# Tayloe_Detector_v3.net
KiCad netlist of a schematic drawn in EAGLE
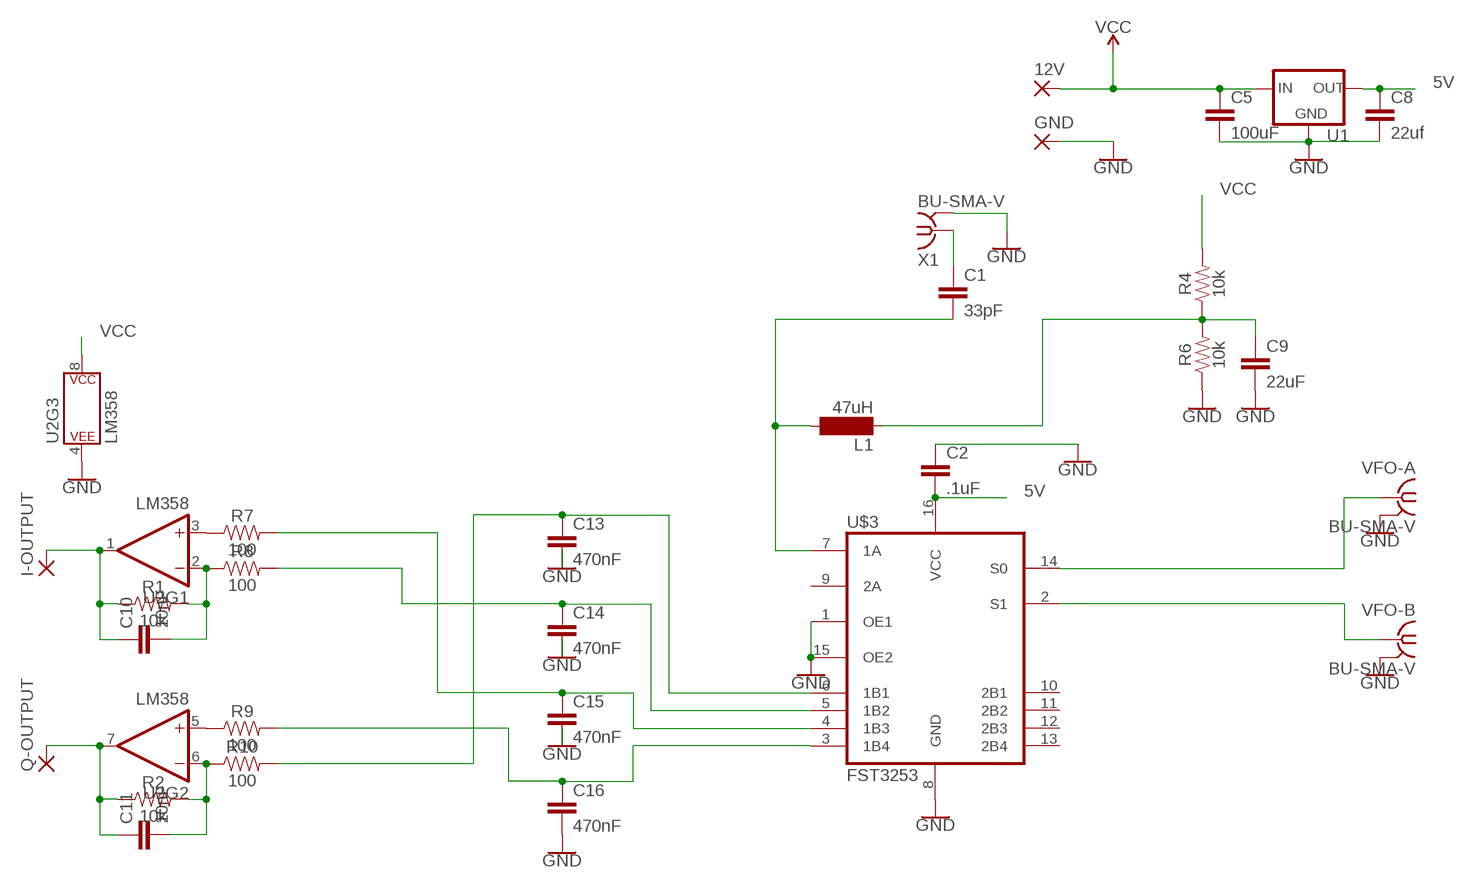
[diagram p0: schematic, sheet 1]

(export (version "E")
  (design (tool "Eeschema 10.0.6"))
  (components
    (comp (ref "12V")
      (value "3,17/1,1")
      (footprint "eagle-import:3,17_1,1")
      (libsource (lib "eagle-import") (part "3,17/1,1"))
    )
    (comp (ref "C1")
      (value "33pF")
      (footprint "eagle-import:C5B3.5")
      (libsource (lib "eagle-import") (part "C5/3.5"))
    )
    (comp (ref "C2")
      (value ".1uF")
      (footprint "eagle-import:C5B3.5")
      (libsource (lib "eagle-import") (part "C5/3.5"))
    )
    (comp (ref "C5")
      (value "100uF")
      (footprint "eagle-import:C5B3.5")
      (libsource (lib "eagle-import") (part "C5/3.5"))
    )
    (comp (ref "C8")
      (value "22uf")
      (footprint "eagle-import:C5B3.5")
      (libsource (lib "eagle-import") (part "C5/3.5"))
    )
    (comp (ref "C9")
      (value "22uF")
      (footprint "eagle-import:C5B3.5")
      (libsource (lib "eagle-import") (part "C5/3.5"))
    )
    (comp (ref "C10")
      (value "10nF")
      (footprint "eagle-import:C5B3.5")
      (libsource (lib "eagle-import") (part "C5/3.5"))
    )
    (comp (ref "C11")
      (value "10nF")
      (footprint "eagle-import:C5B3.5")
      (libsource (lib "eagle-import") (part "C5/3.5"))
    )
    (comp (ref "C13")
      (value "470nF")
      (footprint "eagle-import:C5B3.5")
      (libsource (lib "eagle-import") (part "C5/3.5"))
    )
    (comp (ref "C14")
      (value "470nF")
      (footprint "eagle-import:C5B3.5")
      (libsource (lib "eagle-import") (part "C5/3.5"))
    )
    (comp (ref "C15")
      (value "470nF")
      (footprint "eagle-import:C5B3.5")
      (libsource (lib "eagle-import") (part "C5/3.5"))
    )
    (comp (ref "C16")
      (value "470nF")
      (footprint "eagle-import:C5B3.5")
      (libsource (lib "eagle-import") (part "C5/3.5"))
    )
    (comp (ref "GND")
      (value "3,17/1,1")
      (footprint "eagle-import:3,17_1,1")
      (libsource (lib "eagle-import") (part "3,17/1,1"))
    )
    (comp (ref "I-OUTPUT")
      (value "3,17/1,1")
      (footprint "eagle-import:3,17_1,1")
      (libsource (lib "eagle-import") (part "3,17/1,1"))
    )
    (comp (ref "L1")
      (value "47uH")
      (footprint "eagle-import:BS75")
      (libsource (lib "eagle-import") (part "BS75"))
    )
    (comp (ref "Q-OUTPUT")
      (value "3,17/1,1")
      (footprint "eagle-import:3,17_1,1")
      (libsource (lib "eagle-import") (part "3,17/1,1"))
    )
    (comp (ref "R1")
      (value "10k")
      (footprint "eagle-import:AXIAL-0.3")
      (libsource (lib "eagle-import") (part "1KOHM-HORIZ-1/4W-1%"))
    )
    (comp (ref "R2")
      (value "10k")
      (footprint "eagle-import:AXIAL-0.3")
      (libsource (lib "eagle-import") (part "1KOHM-HORIZ-1/4W-1%"))
    )
    (comp (ref "R4")
      (value "10k")
      (footprint "eagle-import:AXIAL-0.3")
      (libsource (lib "eagle-import") (part "1KOHM-HORIZ-1/4W-1%"))
    )
    (comp (ref "R6")
      (value "10k")
      (footprint "eagle-import:AXIAL-0.3")
      (libsource (lib "eagle-import") (part "1KOHM-HORIZ-1/4W-1%"))
    )
    (comp (ref "R7")
      (value "100")
      (footprint "eagle-import:AXIAL-0.3")
      (libsource (lib "eagle-import") (part "1KOHM-HORIZ-1/4W-1%"))
    )
    (comp (ref "R8")
      (value "100")
      (footprint "eagle-import:AXIAL-0.3")
      (libsource (lib "eagle-import") (part "1KOHM-HORIZ-1/4W-1%"))
    )
    (comp (ref "R9")
      (value "100")
      (footprint "eagle-import:AXIAL-0.3")
      (libsource (lib "eagle-import") (part "1KOHM-HORIZ-1/4W-1%"))
    )
    (comp (ref "R10")
      (value "100")
      (footprint "eagle-import:AXIAL-0.3")
      (libsource (lib "eagle-import") (part "1KOHM-HORIZ-1/4W-1%"))
    )
    (comp (ref "U$3")
      (value "FST3253")
      (footprint "eagle-import:SO16")
      (libsource (lib "eagle-import") (part "FST3253"))
    )
    (comp (ref "U1")
      (value "V_REG_78XXTO-92_UNTESTED")
      (footprint "eagle-import:TO-92")
      (libsource (lib "eagle-import") (part "V_REG_78XXTO-92_UNTESTED"))
    )
    (comp (ref "U2")
      (value "LM358")
      (footprint "eagle-import:DIP08")
      (libsource (lib "eagle-import") (part "LM358"))
    )
    (comp (ref "VFO-A")
      (value "BU-SMA-V")
      (footprint "eagle-import:BU-SMA-V")
      (libsource (lib "eagle-import") (part "BU-SMA-V"))
    )
    (comp (ref "VFO-B")
      (value "BU-SMA-V")
      (footprint "eagle-import:BU-SMA-V")
      (libsource (lib "eagle-import") (part "BU-SMA-V"))
    )
    (comp (ref "X1")
      (value "BU-SMA-V")
      (footprint "eagle-import:BU-SMA-V")
      (libsource (lib "eagle-import") (part "BU-SMA-V"))
    )
  )
  (nets
    (net (code "1") (name "/5V") (class "Default")
      (node (ref "C2") (pin "2") (pinfunction "2_2") (pintype "passive"))
      (node (ref "C8") (pin "1") (pinfunction "1_1") (pintype "passive"))
      (node (ref "U$3") (pin "16") (pinfunction "VCC_16") (pintype "bidirectional"))
      (node (ref "U1") (pin "1") (pinfunction "OUT_1") (pintype "passive"))
    )
    (net (code "2") (name "GND") (class "Default")
      (node (ref "C13") (pin "2") (pinfunction "2_2") (pintype "passive"))
      (node (ref "C14") (pin "2") (pinfunction "2_2") (pintype "passive"))
      (node (ref "C15") (pin "2") (pinfunction "2_2") (pintype "passive"))
      (node (ref "C16") (pin "2") (pinfunction "2_2") (pintype "passive"))
      (node (ref "C2") (pin "1") (pinfunction "1_1") (pintype "passive"))
      (node (ref "C5") (pin "2") (pinfunction "2_2") (pintype "passive"))
      (node (ref "C8") (pin "2") (pinfunction "2_2") (pintype "passive"))
      (node (ref "C9") (pin "2") (pinfunction "2_2") (pintype "passive"))
      (node (ref "GND") (pin "1") (pinfunction "P_1") (pintype "passive"))
      (node (ref "R6") (pin "P$1") (pinfunction "1_P$1") (pintype "passive"))
      (node (ref "U$3") (pin "1") (pinfunction "OE1_1") (pintype "bidirectional"))
      (node (ref "U$3") (pin "15") (pinfunction "OE2_15") (pintype "bidirectional"))
      (node (ref "U$3") (pin "8") (pinfunction "GND_8") (pintype "bidirectional"))
      (node (ref "U1") (pin "2") (pinfunction "GND_2") (pintype "input"))
      (node (ref "U2") (pin "4") (pinfunction "P$V-_4") (pintype "bidirectional"))
      (node (ref "VFO-A") (pin "2") (pinfunction "2_2") (pintype "passive"))
      (node (ref "VFO-A") (pin "3") (pinfunction "2_3") (pintype "passive"))
      (node (ref "VFO-A") (pin "4") (pinfunction "2_4") (pintype "passive"))
      (node (ref "VFO-A") (pin "5") (pinfunction "2_5") (pintype "passive"))
      (node (ref "VFO-B") (pin "2") (pinfunction "2_2") (pintype "passive"))
      (node (ref "VFO-B") (pin "3") (pinfunction "2_3") (pintype "passive"))
      (node (ref "VFO-B") (pin "4") (pinfunction "2_4") (pintype "passive"))
      (node (ref "VFO-B") (pin "5") (pinfunction "2_5") (pintype "passive"))
      (node (ref "X1") (pin "2") (pinfunction "2_2") (pintype "passive"))
      (node (ref "X1") (pin "3") (pinfunction "2_3") (pintype "passive"))
      (node (ref "X1") (pin "4") (pinfunction "2_4") (pintype "passive"))
      (node (ref "X1") (pin "5") (pinfunction "2_5") (pintype "passive"))
    )
    (net (code "3") (name "Net-(C1-Pad1)") (class "Default")
      (node (ref "C1") (pin "1") (pinfunction "1_1") (pintype "passive"))
      (node (ref "X1") (pin "1") (pinfunction "1_1") (pintype "passive"))
    )
    (net (code "4") (name "Net-(I-OUTPUT-P)") (class "Default")
      (node (ref "C10") (pin "1") (pinfunction "1_1") (pintype "passive"))
      (node (ref "I-OUTPUT") (pin "1") (pinfunction "P_1") (pintype "passive"))
      (node (ref "R1") (pin "P$1") (pinfunction "1_P$1") (pintype "passive"))
      (node (ref "U2") (pin "1") (pinfunction "OUT_1") (pintype "output"))
    )
    (net (code "5") (name "Net-(Q-OUTPUT-P)") (class "Default")
      (node (ref "C11") (pin "1") (pinfunction "1_1") (pintype "passive"))
      (node (ref "Q-OUTPUT") (pin "1") (pinfunction "P_1") (pintype "passive"))
      (node (ref "R2") (pin "P$1") (pinfunction "1_P$1") (pintype "passive"))
      (node (ref "U2") (pin "7") (pinfunction "OUT_7") (pintype "output"))
    )
    (net (code "6") (name "Net-(R1-2)") (class "Default")
      (node (ref "C10") (pin "2") (pinfunction "2_2") (pintype "passive"))
      (node (ref "R1") (pin "P$2") (pinfunction "2_P$2") (pintype "passive"))
      (node (ref "R8") (pin "P$1") (pinfunction "1_P$1") (pintype "passive"))
      (node (ref "U2") (pin "2") (pinfunction "-IN_2") (pintype "input"))
    )
    (net (code "7") (name "Net-(R4-1)") (class "Default")
      (node (ref "C9") (pin "1") (pinfunction "1_1") (pintype "passive"))
      (node (ref "L1") (pin "1") (pinfunction "1_1") (pintype "passive"))
      (node (ref "R4") (pin "P$1") (pinfunction "1_P$1") (pintype "passive"))
      (node (ref "R6") (pin "P$2") (pinfunction "2_P$2") (pintype "passive"))
    )
    (net (code "8") (name "Net-(R7-1)") (class "Default")
      (node (ref "R7") (pin "P$1") (pinfunction "1_P$1") (pintype "passive"))
      (node (ref "U2") (pin "3") (pinfunction "+IN_3") (pintype "input"))
    )
    (net (code "9") (name "Net-(R7-2)") (class "Default")
      (node (ref "C15") (pin "1") (pinfunction "1_1") (pintype "passive"))
      (node (ref "R7") (pin "P$2") (pinfunction "2_P$2") (pintype "passive"))
      (node (ref "U$3") (pin "4") (pinfunction "1B3_4") (pintype "output"))
    )
    (net (code "10") (name "Net-(R8-2)") (class "Default")
      (node (ref "C14") (pin "1") (pinfunction "1_1") (pintype "passive"))
      (node (ref "R8") (pin "P$2") (pinfunction "2_P$2") (pintype "passive"))
      (node (ref "U$3") (pin "5") (pinfunction "1B2_5") (pintype "input"))
    )
    (net (code "11") (name "Net-(R9-1)") (class "Default")
      (node (ref "R9") (pin "P$1") (pinfunction "1_P$1") (pintype "passive"))
      (node (ref "U2") (pin "5") (pinfunction "+IN_5") (pintype "input"))
    )
    (net (code "12") (name "Net-(R9-2)") (class "Default")
      (node (ref "C16") (pin "1") (pinfunction "1_1") (pintype "passive"))
      (node (ref "R9") (pin "P$2") (pinfunction "2_P$2") (pintype "passive"))
      (node (ref "U$3") (pin "3") (pinfunction "1B4_3") (pintype "output"))
    )
    (net (code "13") (name "Net-(R10-1)") (class "Default")
      (node (ref "C11") (pin "2") (pinfunction "2_2") (pintype "passive"))
      (node (ref "R10") (pin "P$1") (pinfunction "1_P$1") (pintype "passive"))
      (node (ref "R2") (pin "P$2") (pinfunction "2_P$2") (pintype "passive"))
      (node (ref "U2") (pin "6") (pinfunction "-IN_6") (pintype "input"))
    )
    (net (code "14") (name "Net-(R10-2)") (class "Default")
      (node (ref "C13") (pin "1") (pinfunction "1_1") (pintype "passive"))
      (node (ref "R10") (pin "P$2") (pinfunction "2_P$2") (pintype "passive"))
      (node (ref "U$3") (pin "6") (pinfunction "1B1_6") (pintype "input"))
    )
    (net (code "15") (name "Net-(U$3-1A)") (class "Default")
      (node (ref "C1") (pin "2") (pinfunction "2_2") (pintype "passive"))
      (node (ref "L1") (pin "2") (pinfunction "2_2") (pintype "passive"))
      (node (ref "U$3") (pin "7") (pinfunction "1A_7") (pintype "bidirectional"))
    )
    (net (code "16") (name "Net-(U$3-S0)") (class "Default")
      (node (ref "U$3") (pin "14") (pinfunction "S0_14") (pintype "bidirectional"))
      (node (ref "VFO-A") (pin "1") (pinfunction "1_1") (pintype "passive"))
    )
    (net (code "17") (name "Net-(U$3-S1)") (class "Default")
      (node (ref "U$3") (pin "2") (pinfunction "S1_2") (pintype "bidirectional"))
      (node (ref "VFO-B") (pin "1") (pinfunction "1_1") (pintype "passive"))
    )
    (net (code "18") (name "VCC") (class "Default")
      (node (ref "12V") (pin "1") (pinfunction "P_1") (pintype "passive"))
      (node (ref "C5") (pin "1") (pinfunction "1_1") (pintype "passive"))
      (node (ref "R4") (pin "P$2") (pinfunction "2_P$2") (pintype "passive"))
      (node (ref "U1") (pin "3") (pinfunction "IN_3") (pintype "input"))
      (node (ref "U2") (pin "8") (pinfunction "P$V+_8") (pintype "bidirectional"))
    )
    (net (code "19") (name "unconnected-(U$3-2A-Pad9)") (class "Default")
      (node (ref "U$3") (pin "9") (pinfunction "2A_9") (pintype "bidirectional"))
    )
    (net (code "20") (name "unconnected-(U$3-2B1-Pad10)") (class "Default")
      (node (ref "U$3") (pin "10") (pinfunction "2B1_10") (pintype "output"))
    )
    (net (code "21") (name "unconnected-(U$3-2B2-Pad11)") (class "Default")
      (node (ref "U$3") (pin "11") (pinfunction "2B2_11") (pintype "output"))
    )
    (net (code "22") (name "unconnected-(U$3-2B3-Pad12)") (class "Default")
      (node (ref "U$3") (pin "12") (pinfunction "2B3_12") (pintype "input"))
    )
    (net (code "23") (name "unconnected-(U$3-2B4-Pad13)") (class "Default")
      (node (ref "U$3") (pin "13") (pinfunction "2B4_13") (pintype "input"))
    )
  )
)
